# ADSB_AMP_V3.net
KiCad netlist of a schematic drawn in EAGLE
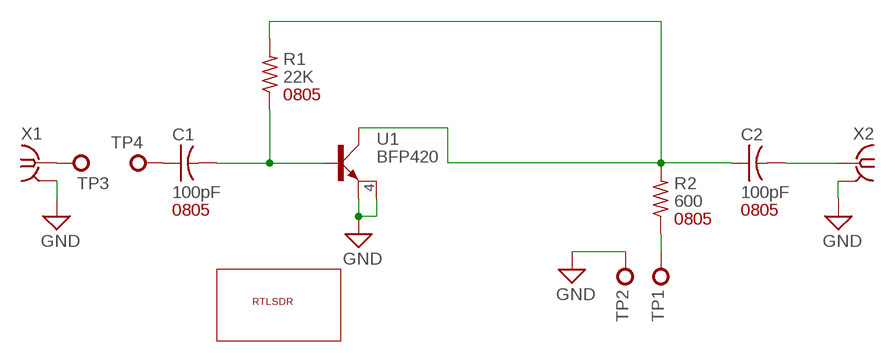
[diagram p0: schematic, sheet 1]

(export (version "E")
  (design (tool "Eeschema 10.0.6"))
  (components
    (comp (ref "C1")
      (value "100pF")
      (footprint "eagle-import:0805")
      (libsource (lib "eagle-import") (part "CAP0805"))
    )
    (comp (ref "C2")
      (value "100pF")
      (footprint "eagle-import:0805")
      (libsource (lib "eagle-import") (part "CAP0805"))
    )
    (comp (ref "R1")
      (value "22K")
      (footprint "eagle-import:0805")
      (libsource (lib "eagle-import") (part "RES0805"))
    )
    (comp (ref "R2")
      (value "600")
      (footprint "eagle-import:0805")
      (libsource (lib "eagle-import") (part "RES0805"))
    )
    (comp (ref "TP1")
      (value "TEST_POINTS76_150")
      (footprint "eagle-import:SMD_76_150")
      (libsource (lib "eagle-import") (part "TEST_POINTS76_150"))
    )
    (comp (ref "TP2")
      (value "TEST_POINTS76_150")
      (footprint "eagle-import:SMD_76_150")
      (libsource (lib "eagle-import") (part "TEST_POINTS76_150"))
    )
    (comp (ref "TP3")
      (value "TEST_POINTS8_8")
      (footprint "eagle-import:SMD_8_8")
      (libsource (lib "eagle-import") (part "TEST_POINTS8_8"))
    )
    (comp (ref "TP4")
      (value "TEST_POINTS8_8")
      (footprint "eagle-import:SMD_8_8")
      (libsource (lib "eagle-import") (part "TEST_POINTS8_8"))
    )
    (comp (ref "U$1")
      (value "RTLSDR-LARGE")
      (footprint "eagle-import:RTLSDR-LARGE")
      (libsource (lib "eagle-import") (part "RTLSDR-LARGE"))
    )
    (comp (ref "U1")
      (value "BFP420")
      (footprint "eagle-import:SOT343_INFINEON")
      (libsource (lib "eagle-import") (part "BFP420"))
    )
    (comp (ref "X1")
      (value "SMA-142-0701-801/806")
      (footprint "eagle-import:J502-ND-142-0701-801_806")
      (fields (field (name "MF") "JOHNSON COMPONENTS") (field (name "MPN") "142-0701-801"))
      (libsource (lib "eagle-import") (part "SMA-142-0701-801/806"))
    )
    (comp (ref "X2")
      (value "SMA-142-0701-801/806")
      (footprint "eagle-import:J502-ND-142-0701-801_806")
      (fields (field (name "MF") "JOHNSON COMPONENTS") (field (name "MPN") "142-0701-801"))
      (libsource (lib "eagle-import") (part "SMA-142-0701-801/806"))
    )
  )
  (nets
    (net (code "1") (name "GND") (class "Default")
      (node (ref "TP2") (pin "1") (pinfunction "MP_1") (pintype "passive"))
      (node (ref "U1") (pin "2") (pinfunction "E1_2") (pintype "passive"))
      (node (ref "U1") (pin "4") (pinfunction "E2_4") (pintype "passive"))
      (node (ref "X1") (pin "G@1") (pinfunction "GND_G@1") (pintype "power_in"))
      (node (ref "X2") (pin "G@1") (pinfunction "GND_G@1") (pintype "power_in"))
    )
    (net (code "2") (name "Net-(C2-Pad2)") (class "Default")
      (node (ref "C2") (pin "2") (pinfunction "2_2") (pintype "passive"))
      (node (ref "X2") (pin "1") (pinfunction "1_1") (pintype "passive"))
    )
    (net (code "3") (name "Net-(TP1-MP)") (class "Default")
      (node (ref "R2") (pin "1") (pinfunction "1_1") (pintype "passive"))
      (node (ref "TP1") (pin "1") (pinfunction "MP_1") (pintype "passive"))
    )
    (net (code "4") (name "Net-(TP3-MP)") (class "Default")
      (node (ref "TP3") (pin "1") (pinfunction "MP_1") (pintype "passive"))
      (node (ref "X1") (pin "1") (pinfunction "1_1") (pintype "passive"))
    )
    (net (code "5") (name "Net-(TP4-MP)") (class "Default")
      (node (ref "C1") (pin "1") (pinfunction "1_1") (pintype "passive"))
      (node (ref "TP4") (pin "1") (pinfunction "MP_1") (pintype "passive"))
    )
    (net (code "6") (name "Net-(U1-B)") (class "Default")
      (node (ref "C1") (pin "2") (pinfunction "2_2") (pintype "passive"))
      (node (ref "R1") (pin "1") (pinfunction "1_1") (pintype "passive"))
      (node (ref "U1") (pin "1") (pinfunction "B_1") (pintype "passive"))
    )
    (net (code "7") (name "Net-(U1-C)") (class "Default")
      (node (ref "C2") (pin "1") (pinfunction "1_1") (pintype "passive"))
      (node (ref "R1") (pin "2") (pinfunction "2_2") (pintype "passive"))
      (node (ref "R2") (pin "2") (pinfunction "2_2") (pintype "passive"))
      (node (ref "U1") (pin "3") (pinfunction "C_3") (pintype "passive"))
    )
  )
)
